# vfd_pt6315.net
KiCad netlist of a schematic drawn in Altium Designer
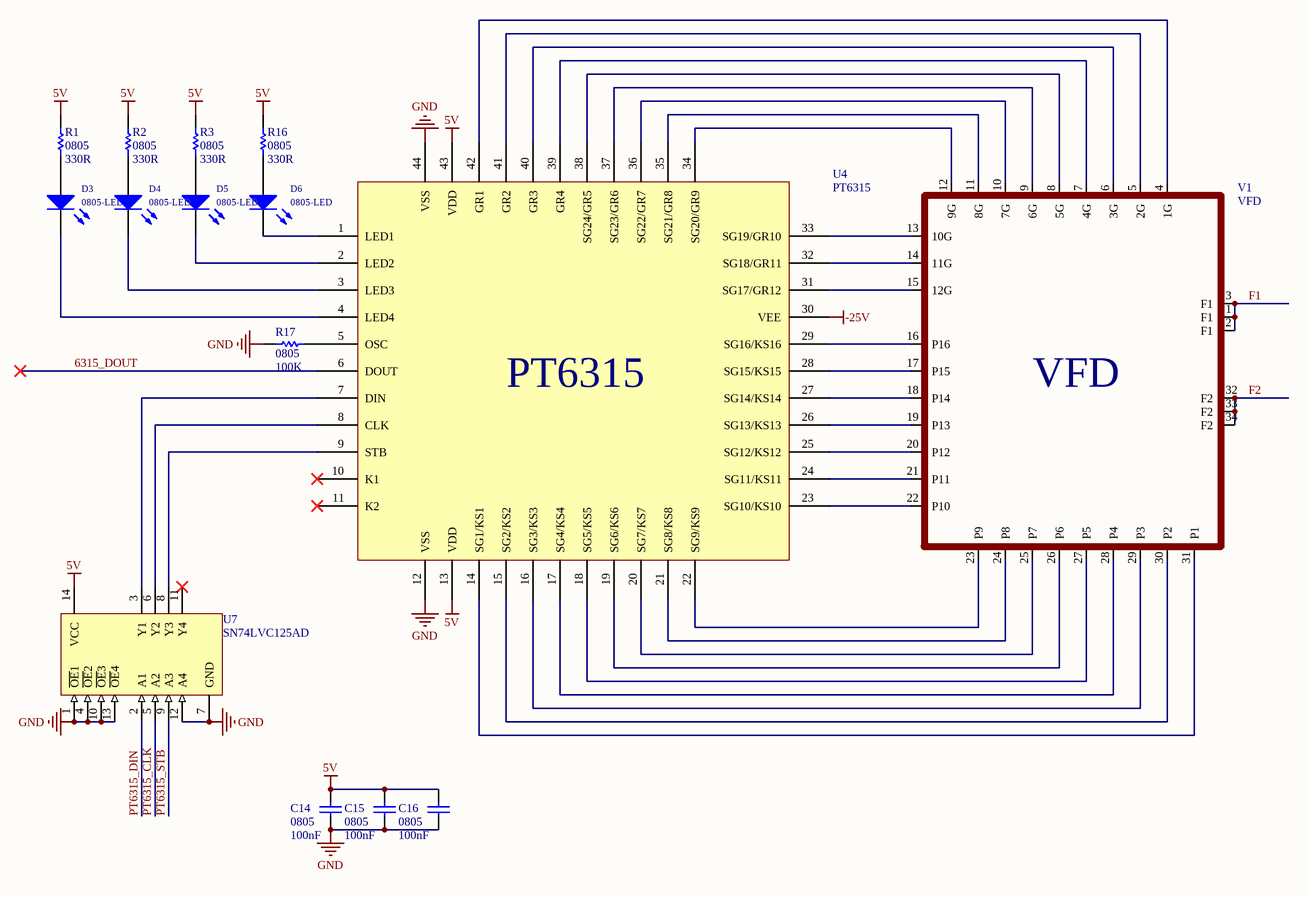
[diagram p0: vfd_pt6315.SchDoc]

(export (version "E")
  (design (tool "Eeschema 10.0.6"))
  (components
    (comp (ref "C14")
      (value "0805")
      (footprint "6-0805_N")
      (description "Capacitor")
      (fields (field (name "ALTIUM_VALUE") "100nF") (field (name "PUBLISHER") "Altium Limited"))
      (libsource (lib "Miscellaneous Devices") (part "CAP"))
    )
    (comp (ref "C15")
      (value "0805")
      (footprint "6-0805_N")
      (description "Capacitor")
      (fields (field (name "ALTIUM_VALUE") "100nF") (field (name "PUBLISHER") "Altium Limited"))
      (libsource (lib "Miscellaneous Devices") (part "CAP"))
    )
    (comp (ref "C16")
      (value "0805")
      (footprint "6-0805_N")
      (description "Capacitor")
      (fields (field (name "ALTIUM_VALUE") "100nF") (field (name "PUBLISHER") "Altium Limited"))
      (libsource (lib "Miscellaneous Devices") (part "CAP"))
    )
    (comp (ref "D3")
      (value "0805-LED")
      (footprint "SMD _LED")
      (description "Typical RED GaAs SMD LED Agilent make")
      (libsource (lib "SpiritLevel_2E") (part "HSMX-C670_1"))
    )
    (comp (ref "D4")
      (value "0805-LED")
      (footprint "SMD _LED")
      (description "Typical RED GaAs SMD LED Agilent make")
      (libsource (lib "SpiritLevel_2E") (part "HSMX-C670_1"))
    )
    (comp (ref "D5")
      (value "0805-LED")
      (footprint "SMD _LED")
      (description "Typical RED GaAs SMD LED Agilent make")
      (libsource (lib "SpiritLevel_2E") (part "HSMX-C670_1"))
    )
    (comp (ref "D6")
      (value "0805-LED")
      (footprint "SMD _LED")
      (description "Typical RED GaAs SMD LED Agilent make")
      (libsource (lib "SpiritLevel_2E") (part "HSMX-C670_1"))
    )
    (comp (ref "R1")
      (value "0805")
      (footprint "6-0805_N")
      (description "Resistor")
      (fields (field (name "ALTIUM_VALUE") "330R") (field (name "PUBLISHER") "Altium Limited"))
      (libsource (lib "Miscellaneous Devices") (part "Res1"))
    )
    (comp (ref "R2")
      (value "0805")
      (footprint "6-0805_N")
      (description "Resistor")
      (fields (field (name "ALTIUM_VALUE") "330R") (field (name "PUBLISHER") "Altium Limited"))
      (libsource (lib "Miscellaneous Devices") (part "Res1"))
    )
    (comp (ref "R3")
      (value "0805")
      (footprint "6-0805_N")
      (description "Resistor")
      (fields (field (name "ALTIUM_VALUE") "330R") (field (name "PUBLISHER") "Altium Limited"))
      (libsource (lib "Miscellaneous Devices") (part "Res1"))
    )
    (comp (ref "R16")
      (value "0805")
      (footprint "6-0805_N")
      (description "Resistor")
      (fields (field (name "ALTIUM_VALUE") "330R") (field (name "PUBLISHER") "Altium Limited"))
      (libsource (lib "Miscellaneous Devices") (part "Res1"))
    )
    (comp (ref "R17")
      (value "0805")
      (footprint "6-0805_N")
      (description "Resistor")
      (fields (field (name "ALTIUM_VALUE") "100K") (field (name "PUBLISHER") "Altium Limited"))
      (libsource (lib "Miscellaneous Devices") (part "Res1"))
    )
    (comp (ref "U4") (value "PT6315") (footprint "LQFP44_10X10X08P") (libsource (lib "vfd") (part "PT6315")))
    (comp (ref "U7")
      (value "SN74LVC125AD")
      (footprint "D014_N")
      (description "Quadruple Bus Buffer Gate with 3-State Outputs")
      (fields (field (name "PUBLISHER") "Altium Limited"))
      (libsource (lib "TI Logic Buffer Line Driver") (part "SN74LVC125AD"))
    )
    (comp (ref "V1")
      (value "VFD")
      (footprint "VFD48-1202FN")
      (description "VFD48-1202FN")
      (libsource (lib "vfd") (part "VFD48-1202FN"))
    )
  )
  (nets
    (net (code "1") (name "-25V") (class "Default")
      (node (ref "U4") (pin "30") (pinfunction "VEE_30") (pintype "passive"))
    )
    (net (code "2") (name "/6315_DOUT") (class "Default")
      (node (ref "U4") (pin "6") (pinfunction "DOUT_6") (pintype "passive+no_connect"))
    )
    (net (code "3") (name "/F1") (class "Default")
      (node (ref "V1") (pin "1") (pinfunction "F1_1") (pintype "passive"))
      (node (ref "V1") (pin "2") (pinfunction "F1_2") (pintype "passive"))
      (node (ref "V1") (pin "3") (pinfunction "F1_3") (pintype "passive"))
    )
    (net (code "4") (name "/F2") (class "Default")
      (node (ref "V1") (pin "32") (pinfunction "F2_32") (pintype "passive"))
      (node (ref "V1") (pin "33") (pinfunction "F2_33") (pintype "passive"))
      (node (ref "V1") (pin "34") (pinfunction "F2_34") (pintype "passive"))
    )
    (net (code "5") (name "/PT6315_CLK") (class "Default")
      (node (ref "U7") (pin "5") (pinfunction "A2_5") (pintype "input"))
    )
    (net (code "6") (name "/PT6315_DIN") (class "Default")
      (node (ref "U7") (pin "2") (pinfunction "A1_2") (pintype "input"))
    )
    (net (code "7") (name "/PT6315_STB") (class "Default")
      (node (ref "U7") (pin "9") (pinfunction "A3_9") (pintype "input"))
    )
    (net (code "8") (name "5V") (class "Default")
      (node (ref "C14") (pin "2") (pinfunction "2_2") (pintype "passive"))
      (node (ref "C15") (pin "2") (pinfunction "2_2") (pintype "passive"))
      (node (ref "C16") (pin "2") (pinfunction "2_2") (pintype "passive"))
      (node (ref "R1") (pin "2") (pinfunction "2_2") (pintype "passive"))
      (node (ref "R16") (pin "2") (pinfunction "2_2") (pintype "passive"))
      (node (ref "R2") (pin "2") (pinfunction "2_2") (pintype "passive"))
      (node (ref "R3") (pin "2") (pinfunction "2_2") (pintype "passive"))
      (node (ref "U4") (pin "13") (pinfunction "VDD_13") (pintype "passive"))
      (node (ref "U4") (pin "43") (pinfunction "VDD_43") (pintype "passive"))
      (node (ref "U7") (pin "14") (pinfunction "VCC_14") (pintype "power_in"))
    )
    (net (code "9") (name "GND") (class "Default")
      (node (ref "C14") (pin "1") (pinfunction "1_1") (pintype "passive"))
      (node (ref "C15") (pin "1") (pinfunction "1_1") (pintype "passive"))
      (node (ref "C16") (pin "1") (pinfunction "1_1") (pintype "passive"))
      (node (ref "R17") (pin "1") (pinfunction "1_1") (pintype "passive"))
      (node (ref "U4") (pin "12") (pinfunction "VSS_12") (pintype "passive"))
      (node (ref "U4") (pin "44") (pinfunction "VSS_44") (pintype "passive"))
      (node (ref "U7") (pin "1") (pinfunction "~{OE}1_1") (pintype "input"))
      (node (ref "U7") (pin "10") (pinfunction "~{OE}3_10") (pintype "input"))
      (node (ref "U7") (pin "12") (pinfunction "A4_12") (pintype "input"))
      (node (ref "U7") (pin "13") (pinfunction "~{OE}4_13") (pintype "input"))
      (node (ref "U7") (pin "4") (pinfunction "~{OE}2_4") (pintype "input"))
      (node (ref "U7") (pin "7") (pinfunction "GND_7") (pintype "power_in"))
    )
    (net (code "10") (name "Net-(D3-A)") (class "Default")
      (node (ref "D3") (pin "1") (pinfunction "A_1") (pintype "passive"))
      (node (ref "R1") (pin "1") (pinfunction "1_1") (pintype "passive"))
    )
    (net (code "11") (name "Net-(D3-K)") (class "Default")
      (node (ref "D3") (pin "2") (pinfunction "K_2") (pintype "passive"))
      (node (ref "U4") (pin "4") (pinfunction "LED4_4") (pintype "passive"))
    )
    (net (code "12") (name "Net-(D4-A)") (class "Default")
      (node (ref "D4") (pin "1") (pinfunction "A_1") (pintype "passive"))
      (node (ref "R2") (pin "1") (pinfunction "1_1") (pintype "passive"))
    )
    (net (code "13") (name "Net-(D4-K)") (class "Default")
      (node (ref "D4") (pin "2") (pinfunction "K_2") (pintype "passive"))
      (node (ref "U4") (pin "3") (pinfunction "LED3_3") (pintype "passive"))
    )
    (net (code "14") (name "Net-(D5-A)") (class "Default")
      (node (ref "D5") (pin "1") (pinfunction "A_1") (pintype "passive"))
      (node (ref "R3") (pin "1") (pinfunction "1_1") (pintype "passive"))
    )
    (net (code "15") (name "Net-(D5-K)") (class "Default")
      (node (ref "D5") (pin "2") (pinfunction "K_2") (pintype "passive"))
      (node (ref "U4") (pin "2") (pinfunction "LED2_2") (pintype "passive"))
    )
    (net (code "16") (name "Net-(D6-A)") (class "Default")
      (node (ref "D6") (pin "1") (pinfunction "A_1") (pintype "passive"))
      (node (ref "R16") (pin "1") (pinfunction "1_1") (pintype "passive"))
    )
    (net (code "17") (name "Net-(D6-K)") (class "Default")
      (node (ref "D6") (pin "2") (pinfunction "K_2") (pintype "passive"))
      (node (ref "U4") (pin "1") (pinfunction "LED1_1") (pintype "passive"))
    )
    (net (code "18") (name "Net-(U4-CLK)") (class "Default")
      (node (ref "U4") (pin "8") (pinfunction "CLK_8") (pintype "passive"))
      (node (ref "U7") (pin "6") (pinfunction "Y2_6") (pintype "tri_state"))
    )
    (net (code "19") (name "Net-(U4-DIN)") (class "Default")
      (node (ref "U4") (pin "7") (pinfunction "DIN_7") (pintype "passive"))
      (node (ref "U7") (pin "3") (pinfunction "Y1_3") (pintype "tri_state"))
    )
    (net (code "20") (name "Net-(U4-GR1)") (class "Default")
      (node (ref "U4") (pin "42") (pinfunction "GR1_42") (pintype "passive"))
      (node (ref "V1") (pin "4") (pinfunction "1G_4") (pintype "passive"))
    )
    (net (code "21") (name "Net-(U4-GR2)") (class "Default")
      (node (ref "U4") (pin "41") (pinfunction "GR2_41") (pintype "passive"))
      (node (ref "V1") (pin "5") (pinfunction "2G_5") (pintype "passive"))
    )
    (net (code "22") (name "Net-(U4-GR3)") (class "Default")
      (node (ref "U4") (pin "40") (pinfunction "GR3_40") (pintype "passive"))
      (node (ref "V1") (pin "6") (pinfunction "3G_6") (pintype "passive"))
    )
    (net (code "23") (name "Net-(U4-GR4)") (class "Default")
      (node (ref "U4") (pin "39") (pinfunction "GR4_39") (pintype "passive"))
      (node (ref "V1") (pin "7") (pinfunction "4G_7") (pintype "passive"))
    )
    (net (code "24") (name "Net-(U4-OSC)") (class "Default")
      (node (ref "R17") (pin "2") (pinfunction "2_2") (pintype "passive"))
      (node (ref "U4") (pin "5") (pinfunction "OSC_5") (pintype "passive"))
    )
    (net (code "25") (name "Net-(U4-SG1{slash}KS1)") (class "Default")
      (node (ref "U4") (pin "14") (pinfunction "SG1/KS1_14") (pintype "passive"))
      (node (ref "V1") (pin "31") (pinfunction "P1_31") (pintype "passive"))
    )
    (net (code "26") (name "Net-(U4-SG2{slash}KS2)") (class "Default")
      (node (ref "U4") (pin "15") (pinfunction "SG2/KS2_15") (pintype "passive"))
      (node (ref "V1") (pin "30") (pinfunction "P2_30") (pintype "passive"))
    )
    (net (code "27") (name "Net-(U4-SG3{slash}KS3)") (class "Default")
      (node (ref "U4") (pin "16") (pinfunction "SG3/KS3_16") (pintype "passive"))
      (node (ref "V1") (pin "29") (pinfunction "P3_29") (pintype "passive"))
    )
    (net (code "28") (name "Net-(U4-SG4{slash}KS4)") (class "Default")
      (node (ref "U4") (pin "17") (pinfunction "SG4/KS4_17") (pintype "passive"))
      (node (ref "V1") (pin "28") (pinfunction "P4_28") (pintype "passive"))
    )
    (net (code "29") (name "Net-(U4-SG5{slash}KS5)") (class "Default")
      (node (ref "U4") (pin "18") (pinfunction "SG5/KS5_18") (pintype "passive"))
      (node (ref "V1") (pin "27") (pinfunction "P5_27") (pintype "passive"))
    )
    (net (code "30") (name "Net-(U4-SG6{slash}KS6)") (class "Default")
      (node (ref "U4") (pin "19") (pinfunction "SG6/KS6_19") (pintype "passive"))
      (node (ref "V1") (pin "26") (pinfunction "P6_26") (pintype "passive"))
    )
    (net (code "31") (name "Net-(U4-SG7{slash}KS7)") (class "Default")
      (node (ref "U4") (pin "20") (pinfunction "SG7/KS7_20") (pintype "passive"))
      (node (ref "V1") (pin "25") (pinfunction "P7_25") (pintype "passive"))
    )
    (net (code "32") (name "Net-(U4-SG8{slash}KS8)") (class "Default")
      (node (ref "U4") (pin "21") (pinfunction "SG8/KS8_21") (pintype "passive"))
      (node (ref "V1") (pin "24") (pinfunction "P8_24") (pintype "passive"))
    )
    (net (code "33") (name "Net-(U4-SG9{slash}KS9)") (class "Default")
      (node (ref "U4") (pin "22") (pinfunction "SG9/KS9_22") (pintype "passive"))
      (node (ref "V1") (pin "23") (pinfunction "P9_23") (pintype "passive"))
    )
    (net (code "34") (name "Net-(U4-SG10{slash}KS10)") (class "Default")
      (node (ref "U4") (pin "23") (pinfunction "SG10/KS10_23") (pintype "passive"))
      (node (ref "V1") (pin "22") (pinfunction "P10_22") (pintype "passive"))
    )
    (net (code "35") (name "Net-(U4-SG11{slash}KS11)") (class "Default")
      (node (ref "U4") (pin "24") (pinfunction "SG11/KS11_24") (pintype "passive"))
      (node (ref "V1") (pin "21") (pinfunction "P11_21") (pintype "passive"))
    )
    (net (code "36") (name "Net-(U4-SG12{slash}KS12)") (class "Default")
      (node (ref "U4") (pin "25") (pinfunction "SG12/KS12_25") (pintype "passive"))
      (node (ref "V1") (pin "20") (pinfunction "P12_20") (pintype "passive"))
    )
    (net (code "37") (name "Net-(U4-SG13{slash}KS13)") (class "Default")
      (node (ref "U4") (pin "26") (pinfunction "SG13/KS13_26") (pintype "passive"))
      (node (ref "V1") (pin "19") (pinfunction "P13_19") (pintype "passive"))
    )
    (net (code "38") (name "Net-(U4-SG14{slash}KS14)") (class "Default")
      (node (ref "U4") (pin "27") (pinfunction "SG14/KS14_27") (pintype "passive"))
      (node (ref "V1") (pin "18") (pinfunction "P14_18") (pintype "passive"))
    )
    (net (code "39") (name "Net-(U4-SG15{slash}KS15)") (class "Default")
      (node (ref "U4") (pin "28") (pinfunction "SG15/KS15_28") (pintype "passive"))
      (node (ref "V1") (pin "17") (pinfunction "P15_17") (pintype "passive"))
    )
    (net (code "40") (name "Net-(U4-SG16{slash}KS16)") (class "Default")
      (node (ref "U4") (pin "29") (pinfunction "SG16/KS16_29") (pintype "passive"))
      (node (ref "V1") (pin "16") (pinfunction "P16_16") (pintype "passive"))
    )
    (net (code "41") (name "Net-(U4-SG17{slash}GR12)") (class "Default")
      (node (ref "U4") (pin "31") (pinfunction "SG17/GR12_31") (pintype "passive"))
      (node (ref "V1") (pin "15") (pinfunction "12G_15") (pintype "passive"))
    )
    (net (code "42") (name "Net-(U4-SG18{slash}GR11)") (class "Default")
      (node (ref "U4") (pin "32") (pinfunction "SG18/GR11_32") (pintype "passive"))
      (node (ref "V1") (pin "14") (pinfunction "11G_14") (pintype "passive"))
    )
    (net (code "43") (name "Net-(U4-SG19{slash}GR10)") (class "Default")
      (node (ref "U4") (pin "33") (pinfunction "SG19/GR10_33") (pintype "passive"))
      (node (ref "V1") (pin "13") (pinfunction "10G_13") (pintype "passive"))
    )
    (net (code "44") (name "Net-(U4-SG20{slash}GR9)") (class "Default")
      (node (ref "U4") (pin "34") (pinfunction "SG20/GR9_34") (pintype "passive"))
      (node (ref "V1") (pin "12") (pinfunction "9G_12") (pintype "passive"))
    )
    (net (code "45") (name "Net-(U4-SG21{slash}GR8)") (class "Default")
      (node (ref "U4") (pin "35") (pinfunction "SG21/GR8_35") (pintype "passive"))
      (node (ref "V1") (pin "11") (pinfunction "8G_11") (pintype "passive"))
    )
    (net (code "46") (name "Net-(U4-SG22{slash}GR7)") (class "Default")
      (node (ref "U4") (pin "36") (pinfunction "SG22/GR7_36") (pintype "passive"))
      (node (ref "V1") (pin "10") (pinfunction "7G_10") (pintype "passive"))
    )
    (net (code "47") (name "Net-(U4-SG23{slash}GR6)") (class "Default")
      (node (ref "U4") (pin "37") (pinfunction "SG23/GR6_37") (pintype "passive"))
      (node (ref "V1") (pin "9") (pinfunction "6G_9") (pintype "passive"))
    )
    (net (code "48") (name "Net-(U4-SG24{slash}GR5)") (class "Default")
      (node (ref "U4") (pin "38") (pinfunction "SG24/GR5_38") (pintype "passive"))
      (node (ref "V1") (pin "8") (pinfunction "5G_8") (pintype "passive"))
    )
    (net (code "49") (name "Net-(U4-STB)") (class "Default")
      (node (ref "U4") (pin "9") (pinfunction "STB_9") (pintype "passive"))
      (node (ref "U7") (pin "8") (pinfunction "Y3_8") (pintype "tri_state"))
    )
    (net (code "50") (name "unconnected-(U4-K1-Pad10)") (class "Default")
      (node (ref "U4") (pin "10") (pinfunction "K1_10") (pintype "passive+no_connect"))
    )
    (net (code "51") (name "unconnected-(U4-K2-Pad11)") (class "Default")
      (node (ref "U4") (pin "11") (pinfunction "K2_11") (pintype "passive+no_connect"))
    )
    (net (code "52") (name "unconnected-(U7-Y4-Pad11)") (class "Default")
      (node (ref "U7") (pin "11") (pinfunction "Y4_11") (pintype "tri_state+no_connect"))
    )
  )
)
